# buzzer.net
KiCad netlist of a schematic drawn in Altium Designer
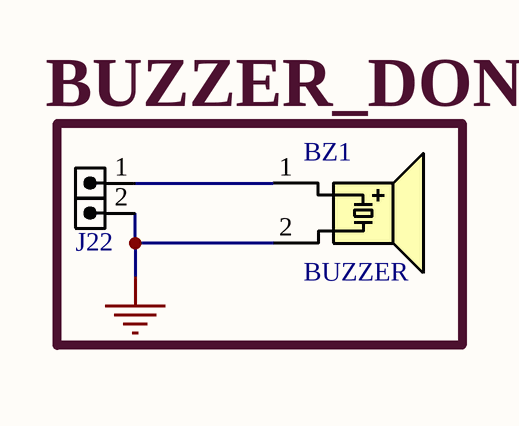
[diagram p0: buzzer.SchDoc]

(export (version "E")
  (design (tool "Eeschema 10.0.6"))
  (components
    (comp (ref "BZ1")
      (value "BUZZER")
      (footprint "BZ_C9")
      (description "Buzzer, 9mm, Magnetic Transducer")
      (fields (field (name "MANF") "Mallory") (field (name "MANF_P#") "PB-09N23P-03Q"))
      (libsource (lib "audio_mic_spk") (part "BUZZER_C9"))
    )
    (comp (ref "J22")
      (value "HDRM2")
      (footprint "HDR_M_1X2")
      (description "CONN, HEADER, Male, pitch: 2.54mm, 2POS")
      (libsource (lib "conn_header_2.54mm_st") (part "HDR_M_1X2"))
    )
  )
  (nets
    (net (code "1") (name "GND") (class "Default")
      (node (ref "BZ1") (pin "2") (pinfunction "B_2") (pintype "passive"))
      (node (ref "J22") (pin "2") (pinfunction "2_2") (pintype "passive"))
    )
    (net (code "2") (name "Net-(BZ1-A)") (class "Default")
      (node (ref "BZ1") (pin "1") (pinfunction "A_1") (pintype "passive"))
      (node (ref "J22") (pin "1") (pinfunction "1_1") (pintype "passive"))
    )
  )
)
